# SNES_TST_Sheet5.net
KiCad netlist of a schematic drawn in Altium Designer
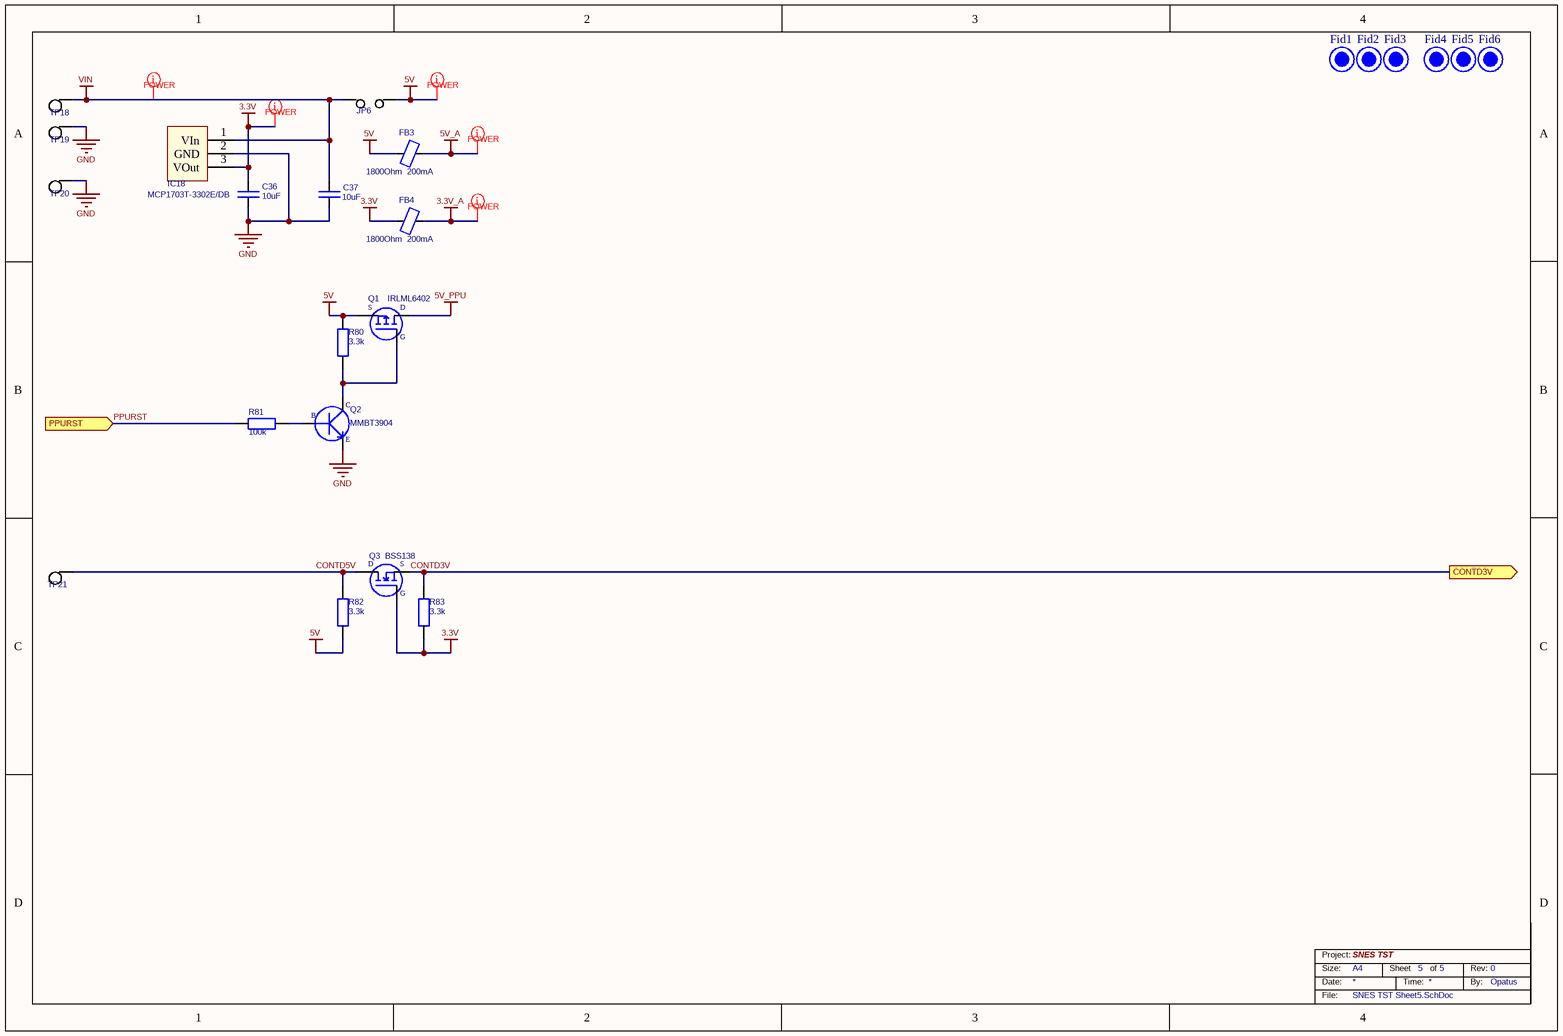
[diagram p0: SNES TST Sheet5.SchDoc]

(export (version "E")
  (design (tool "Eeschema 10.0.6"))
  (components
    (comp (ref "C36")
      (value "10uF")
      (footprint "Cap_0805_Chip")
      (fields (field (name "TOLERANCE") "+-20%"))
      (libsource (lib "PCB") (part "Capacitor"))
    )
    (comp (ref "C37")
      (value "10uF")
      (footprint "Cap_1206_Chip")
      (fields (field (name "TOLERANCE") "+-20%"))
      (libsource (lib "PCB") (part "Capacitor"))
    )
    (comp (ref "FB3")
      (value "1800Ohm  200mA")
      (footprint "Ind_0402_Chip")
      (fields (field (name "MANUFACTURER_PART_NUMBER") "MMZ1005S182ET000"))
      (libsource (lib "PCB") (part "Ferrite Bead"))
    )
    (comp (ref "FB4")
      (value "1800Ohm  200mA")
      (footprint "Ind_0402_Chip")
      (fields (field (name "MANUFACTURER_PART_NUMBER") "MMZ1005S182ET000"))
      (libsource (lib "PCB") (part "Ferrite Bead"))
    )
    (comp (ref "Fid1")
      (value "Fiducial")
      (footprint "Fiducial_1_side")
      (libsource (lib "PCB") (part "Fiducial"))
    )
    (comp (ref "Fid2")
      (value "Fiducial")
      (footprint "Fiducial_1_side")
      (libsource (lib "PCB") (part "Fiducial"))
    )
    (comp (ref "Fid3")
      (value "Fiducial")
      (footprint "Fiducial_1_side")
      (libsource (lib "PCB") (part "Fiducial"))
    )
    (comp (ref "Fid4")
      (value "Fiducial")
      (footprint "Fiducial_1_side")
      (libsource (lib "PCB") (part "Fiducial"))
    )
    (comp (ref "Fid5")
      (value "Fiducial")
      (footprint "Fiducial_1_side")
      (libsource (lib "PCB") (part "Fiducial"))
    )
    (comp (ref "Fid6")
      (value "Fiducial")
      (footprint "Fiducial_1_side")
      (libsource (lib "PCB") (part "Fiducial"))
    )
    (comp (ref "IC18")
      (value "MCP1703T")
      (footprint "SOT223-3")
      (description "3.3V Regulator")
      (fields (field (name "MANUFACTURER_PART_NUMBER") "MCP1703T-3302E/DB"))
      (libsource (lib "PCB") (part "MCP1703 SOT223"))
    )
    (comp (ref "JP6") (value "Jumper") (footprint "Jumper Big") (libsource (lib "PCB") (part "Jumper")))
    (comp (ref "Q1") (value "IRLML6402") (footprint "SOT23_FET") (libsource (lib "PCB") (part "Mosfet1")))
    (comp (ref "Q2") (value "MMBT3904") (footprint "SOT23_Transistor") (libsource (lib "PCB") (part "T_NPN")))
    (comp (ref "Q3") (value "BSS138") (footprint "SOT23_FET") (libsource (lib "PCB") (part "Mosfet N")))
    (comp (ref "R80")
      (value "3.3k")
      (footprint "Res_0402_Chip")
      (fields (field (name "TOLERANCE") "+-1%"))
      (libsource (lib "PCB") (part "R"))
    )
    (comp (ref "R81")
      (value "100k")
      (footprint "Res_0402_Chip")
      (fields (field (name "TOLERANCE") "+-1%"))
      (libsource (lib "") (part "R_1"))
    )
    (comp (ref "R82")
      (value "3.3k")
      (footprint "Res_0402_Chip")
      (fields (field (name "TOLERANCE") "+-1%"))
      (libsource (lib "PCB") (part "R"))
    )
    (comp (ref "R83")
      (value "3.3k")
      (footprint "Res_0402_Chip")
      (fields (field (name "TOLERANCE") "+-1%"))
      (libsource (lib "PCB") (part "R"))
    )
    (comp (ref "TP18")
      (value "Pin Connector")
      (footprint "Pin Connector Small")
      (libsource (lib "PCB") (part "Pin Connector"))
    )
    (comp (ref "TP19")
      (value "Pin Connector")
      (footprint "Pin Connector Small")
      (libsource (lib "PCB") (part "Pin Connector"))
    )
    (comp (ref "TP20")
      (value "Pin Connector")
      (footprint "Pin Connector Small")
      (libsource (lib "PCB") (part "Pin Connector"))
    )
    (comp (ref "TP21")
      (value "Pin Connector")
      (footprint "Pin Connector Small")
      (libsource (lib "PCB") (part "Pin Connector"))
    )
  )
  (nets
    (net (code "1") (name "/CONTD3V") (class "Default")
      (node (ref "Q3") (pin "S") (pinfunction "S_S") (pintype "passive"))
      (node (ref "R83") (pin "1") (pintype "passive"))
    )
    (net (code "2") (name "/CONTD5V") (class "Default")
      (node (ref "Q3") (pin "D") (pinfunction "D_D") (pintype "passive"))
      (node (ref "R82") (pin "1") (pintype "passive"))
      (node (ref "TP21") (pin "1") (pinfunction "0_1") (pintype "passive"))
    )
    (net (code "3") (name "/PPURST") (class "Default") (node (ref "R81") (pin "1") (pintype "passive")))
    (net (code "4") (name "3.3V") (class "Default")
      (node (ref "C36") (pin "2") (pintype "passive"))
      (node (ref "FB4") (pin "1") (pintype "passive"))
      (node (ref "IC18") (pin "3") (pinfunction "VOut_3") (pintype "passive"))
      (node (ref "Q3") (pin "G") (pinfunction "G_G") (pintype "passive"))
      (node (ref "R83") (pin "2") (pintype "passive"))
    )
    (net (code "5") (name "3.3V_A") (class "Default") (node (ref "FB4") (pin "2") (pintype "passive")))
    (net (code "6") (name "5V") (class "Default")
      (node (ref "FB3") (pin "1") (pintype "passive"))
      (node (ref "JP6") (pin "1") (pinfunction "0_1") (pintype "passive"))
      (node (ref "Q1") (pin "S") (pinfunction "S_S") (pintype "passive"))
      (node (ref "R80") (pin "1") (pintype "passive"))
      (node (ref "R82") (pin "2") (pintype "passive"))
    )
    (net (code "7") (name "5V_A") (class "Default") (node (ref "FB3") (pin "2") (pintype "passive")))
    (net (code "8") (name "5V_PPU") (class "Default")
      (node (ref "Q1") (pin "D") (pinfunction "D_D") (pintype "passive"))
    )
    (net (code "9") (name "GND") (class "Default")
      (node (ref "C36") (pin "1") (pintype "passive"))
      (node (ref "C37") (pin "1") (pintype "passive"))
      (node (ref "IC18") (pin "2") (pinfunction "GND_2") (pintype "passive"))
      (node (ref "Q2") (pin "E") (pinfunction "E_E") (pintype "passive"))
      (node (ref "TP19") (pin "1") (pinfunction "0_1") (pintype "passive"))
      (node (ref "TP20") (pin "1") (pinfunction "0_1") (pintype "passive"))
    )
    (net (code "10") (name "Net-(Q1-PadG)") (class "Default")
      (node (ref "Q1") (pin "G") (pinfunction "G_G") (pintype "passive"))
      (node (ref "Q2") (pin "C") (pinfunction "C_C") (pintype "passive"))
      (node (ref "R80") (pin "2") (pintype "passive"))
    )
    (net (code "11") (name "Net-(Q2-PadB)") (class "Default")
      (node (ref "Q2") (pin "B") (pinfunction "B_B") (pintype "passive"))
      (node (ref "R81") (pin "2") (pintype "passive"))
    )
    (net (code "12") (name "VIN") (class "Default")
      (node (ref "C37") (pin "2") (pintype "passive"))
      (node (ref "IC18") (pin "1") (pinfunction "VIn_1") (pintype "passive"))
      (node (ref "JP6") (pin "2") (pinfunction "0_2") (pintype "passive"))
      (node (ref "TP18") (pin "1") (pinfunction "0_1") (pintype "passive"))
    )
  )
)
